# cap_mother_v1_0.net
KiCad netlist of a schematic drawn in EAGLE
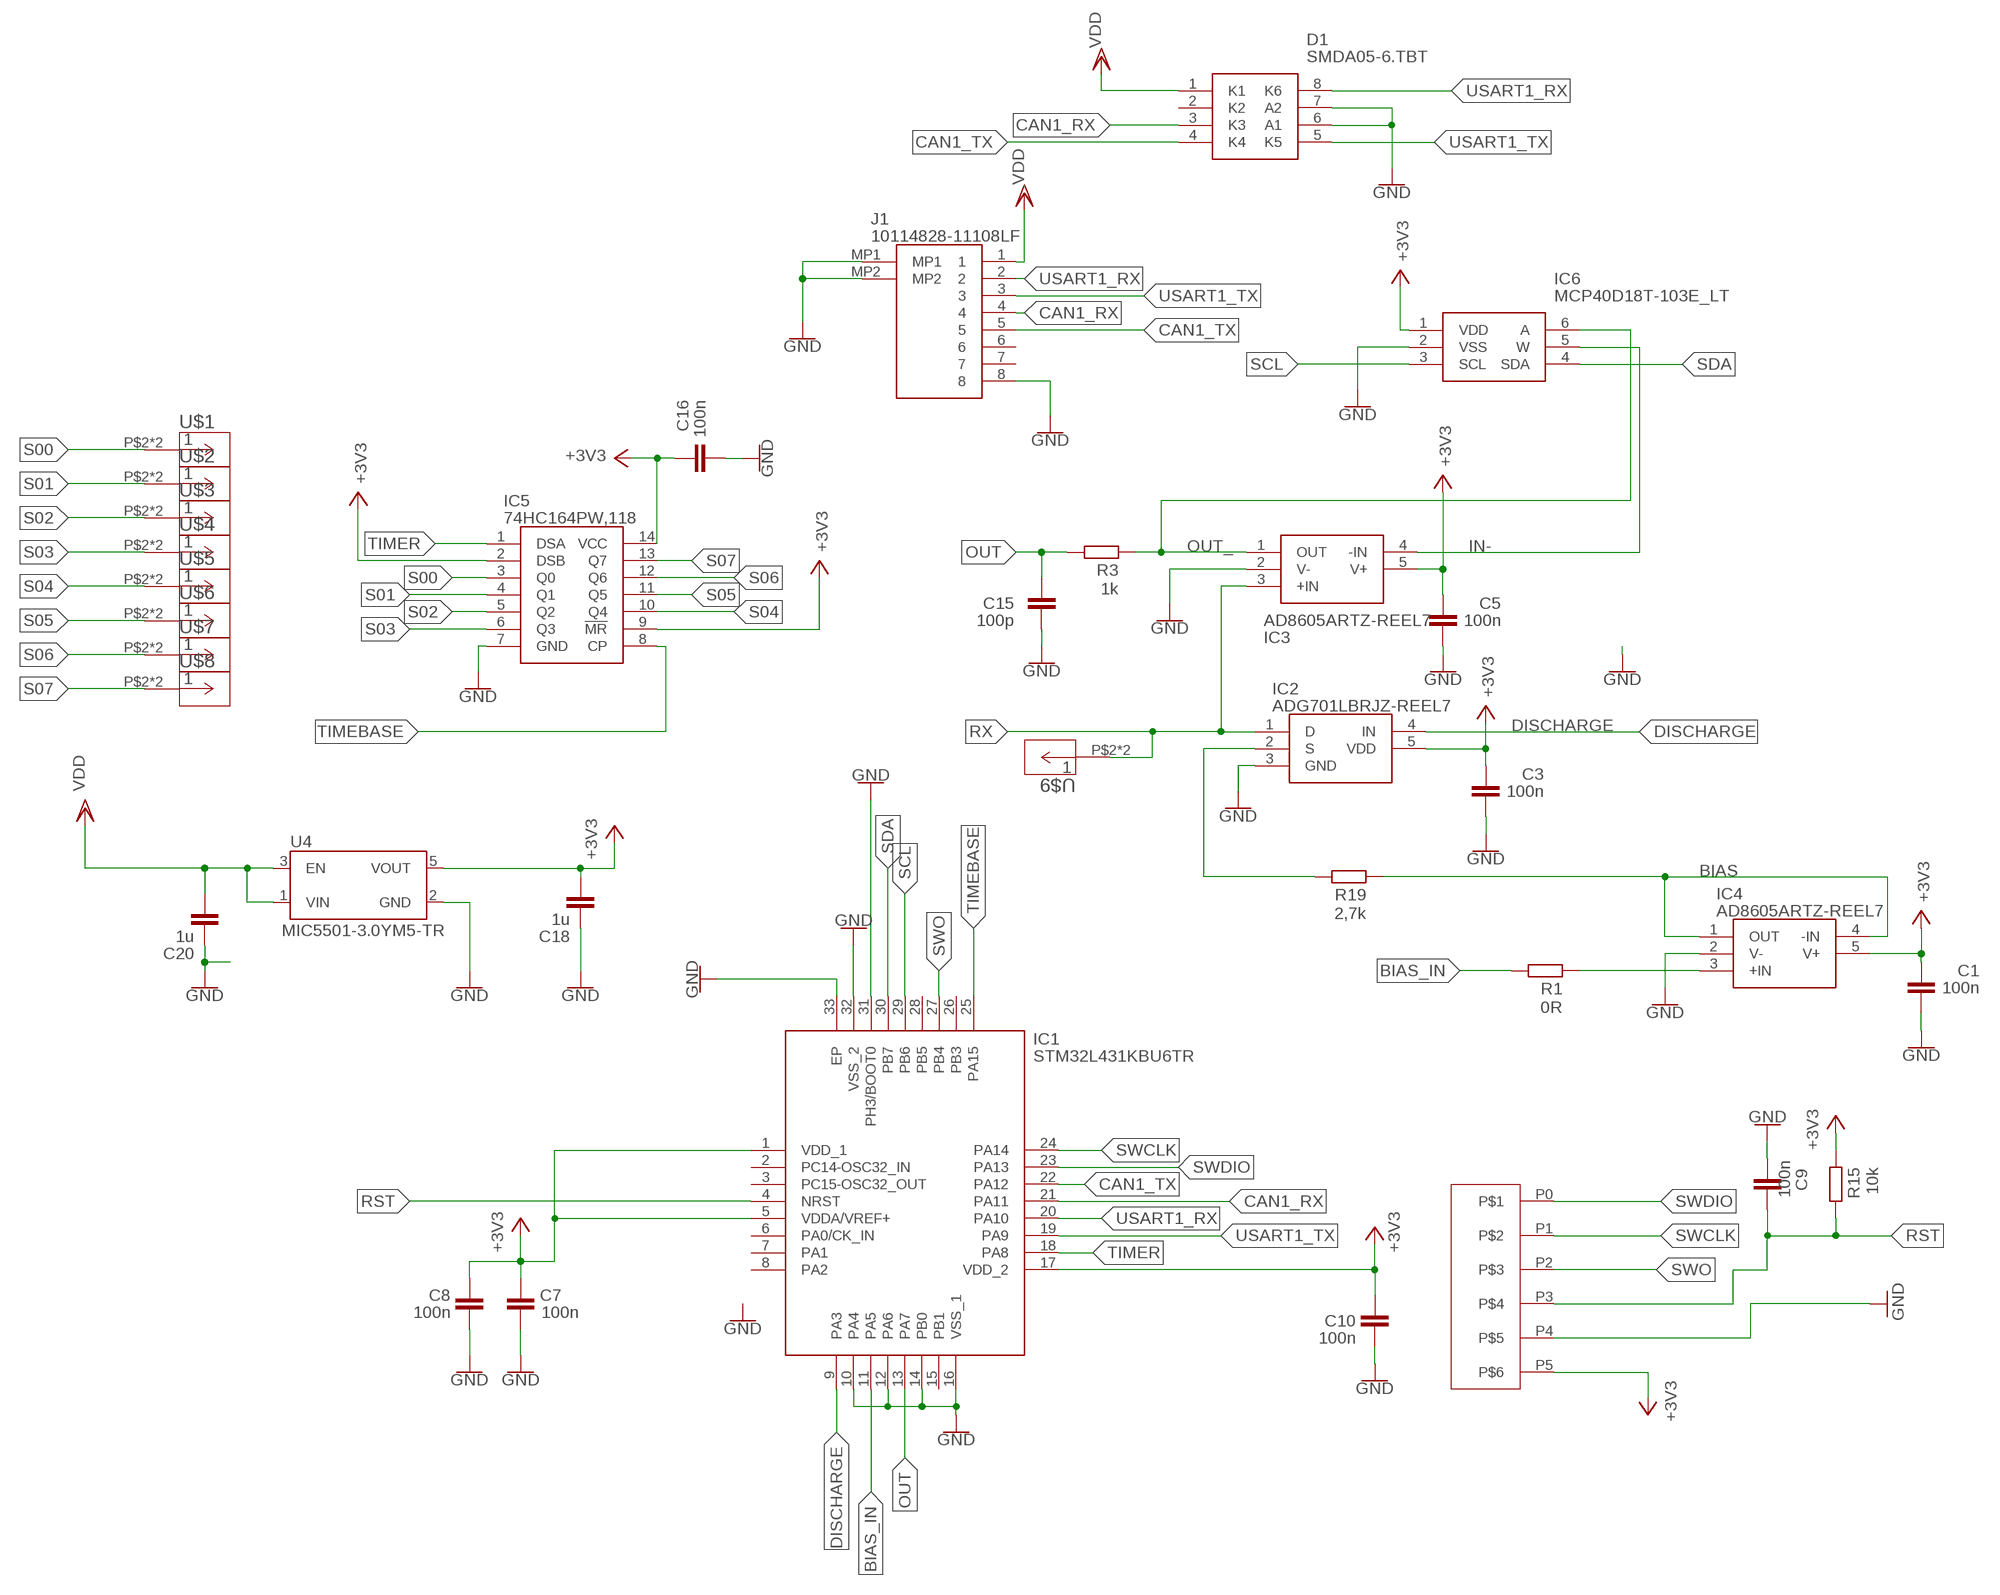
[diagram p0: schematic, sheet 1]

(export (version "E")
  (design (tool "Eeschema 10.0.6"))
  (components
    (comp (ref "C1")
      (value "100n")
      (footprint "eagle-import:C0603K")
      (libsource (lib "eagle-import") (part "rcl_334_C-EUC0603K"))
    )
    (comp (ref "C3")
      (value "100n")
      (footprint "eagle-import:C0603K")
      (libsource (lib "eagle-import") (part "rcl_334_C-EUC0603K"))
    )
    (comp (ref "C5")
      (value "100n")
      (footprint "eagle-import:C0603K")
      (libsource (lib "eagle-import") (part "rcl_334_C-EUC0603K"))
    )
    (comp (ref "C7")
      (value "100n")
      (footprint "eagle-import:C0603K")
      (libsource (lib "eagle-import") (part "rcl_334_C-EUC0603K"))
    )
    (comp (ref "C8")
      (value "100n")
      (footprint "eagle-import:C0603K")
      (libsource (lib "eagle-import") (part "rcl_334_C-EUC0603K"))
    )
    (comp (ref "C9")
      (value "100n")
      (footprint "eagle-import:C0603")
      (libsource (lib "eagle-import") (part "C-EUC0603"))
    )
    (comp (ref "C10")
      (value "100n")
      (footprint "eagle-import:C0603K")
      (libsource (lib "eagle-import") (part "rcl_334_C-EUC0603K"))
    )
    (comp (ref "C15")
      (value "100p")
      (footprint "eagle-import:C0603")
      (libsource (lib "eagle-import") (part "C-EUC0603"))
    )
    (comp (ref "C16")
      (value "100n")
      (footprint "eagle-import:C0603K")
      (libsource (lib "eagle-import") (part "rcl_334_C-EUC0603K"))
    )
    (comp (ref "C18")
      (value "1u")
      (footprint "eagle-import:C0603K")
      (libsource (lib "eagle-import") (part "rcl_334_C-EUC0603K"))
    )
    (comp (ref "C20")
      (value "1u")
      (footprint "eagle-import:C0603")
      (libsource (lib "eagle-import") (part "C-EUC0603"))
    )
    (comp (ref "D1")
      (value "SMDA05-6.TBT")
      (footprint "eagle-import:SOIC127P600X175-8N")
      (fields (field (name "MOUSER_PART_NUMBER") "947-SMDA05-6.TBT"))
      (libsource (lib "eagle-import") (part "SMDA05-6.TBT"))
    )
    (comp (ref "IC1")
      (value "STM32L431KBU6TR")
      (footprint "eagle-import:QFN50P500X500X60-33N")
      (fields (field (name "MOUSER_PART_NUMBER") "511-STM32L431KBU6TR"))
      (libsource (lib "eagle-import") (part "STM32L431KBU6TR"))
    )
    (comp (ref "IC2")
      (value "ADG701LBRJZ-REEL7")
      (footprint "eagle-import:SOT95P280X145-5N")
      (fields (field (name "MOUSER_PART_NUMBER") "584-ADG701LBRJZ-R7"))
      (libsource (lib "eagle-import") (part "ADG701LBRJZ-REEL7"))
    )
    (comp (ref "IC3")
      (value "AD8605ARTZ-REEL7")
      (footprint "eagle-import:SOT95P280X145-5N")
      (fields (field (name "MOUSER_PART_NUMBER") "584-AD8605ARTZ-R7"))
      (libsource (lib "eagle-import") (part "AD8605ARTZ-REEL7"))
    )
    (comp (ref "IC4")
      (value "AD8605ARTZ-REEL7")
      (footprint "eagle-import:SOT95P280X145-5N")
      (fields (field (name "MOUSER_PART_NUMBER") "584-AD8605ARTZ-R7"))
      (libsource (lib "eagle-import") (part "AD8605ARTZ-REEL7"))
    )
    (comp (ref "IC5")
      (value "74HC164PW,118")
      (footprint "eagle-import:SOP65P640X110-14N")
      (fields (field (name "MOUSER_PART_NUMBER") "771-74HC164PW-T"))
      (libsource (lib "eagle-import") (part "74HC164PW,118"))
    )
    (comp (ref "IC6")
      (value "MCP40D18T-103E_LT")
      (footprint "eagle-import:SOT65P210X110-6N")
      (fields
        (field (name "MANUFACTURER_PART_NUMBER") "MCP40D18T-103E/LT")
        (field (name "MOUSER_PART_NUMBER") "579-MCP40D18T103E/LT")
      )
      (libsource (lib "eagle-import") (part "MCP40D18T-103E_LT"))
    )
    (comp (ref "J1")
      (value "10114828-11108LF")
      (footprint "eagle-import:1011482811108LF")
      (fields (field (name "MOUSER_PART_NUMBER") "649-10114828-11108LF"))
      (libsource (lib "eagle-import") (part "10114828-11108LF"))
    )
    (comp (ref "R1")
      (value "0R")
      (footprint "eagle-import:R0603")
      (libsource (lib "eagle-import") (part "R-EU_R0603"))
    )
    (comp (ref "R3")
      (value "1k")
      (footprint "eagle-import:R0603")
      (libsource (lib "eagle-import") (part "R-EU_R0603"))
    )
    (comp (ref "R15")
      (value "10k")
      (footprint "eagle-import:R0603")
      (libsource (lib "eagle-import") (part "R-EU_R0603"))
    )
    (comp (ref "R19")
      (value "2,7k")
      (footprint "eagle-import:R0603")
      (libsource (lib "eagle-import") (part "R-EU_R0603"))
    )
    (comp (ref "U$1")
      (value "CAST_HOLE_1X1SHORT")
      (footprint "eagle-import:CASTELATED_HOLE_SHORT")
      (libsource (lib "eagle-import") (part "CAST_HOLE_1X1SHORT"))
    )
    (comp (ref "U$2")
      (value "CAST_HOLE_1X1SHORT")
      (footprint "eagle-import:CASTELATED_HOLE_SHORT")
      (libsource (lib "eagle-import") (part "CAST_HOLE_1X1SHORT"))
    )
    (comp (ref "U$3")
      (value "CAST_HOLE_1X1SHORT")
      (footprint "eagle-import:CASTELATED_HOLE_SHORT")
      (libsource (lib "eagle-import") (part "CAST_HOLE_1X1SHORT"))
    )
    (comp (ref "U$4")
      (value "CAST_HOLE_1X1SHORT")
      (footprint "eagle-import:CASTELATED_HOLE_SHORT")
      (libsource (lib "eagle-import") (part "CAST_HOLE_1X1SHORT"))
    )
    (comp (ref "U$5")
      (value "CAST_HOLE_1X1SHORT")
      (footprint "eagle-import:CASTELATED_HOLE_SHORT")
      (libsource (lib "eagle-import") (part "CAST_HOLE_1X1SHORT"))
    )
    (comp (ref "U$6")
      (value "CAST_HOLE_1X1SHORT")
      (footprint "eagle-import:CASTELATED_HOLE_SHORT")
      (libsource (lib "eagle-import") (part "CAST_HOLE_1X1SHORT"))
    )
    (comp (ref "U$7")
      (value "CAST_HOLE_1X1SHORT")
      (footprint "eagle-import:CASTELATED_HOLE_SHORT")
      (libsource (lib "eagle-import") (part "CAST_HOLE_1X1SHORT"))
    )
    (comp (ref "U$8")
      (value "CAST_HOLE_1X1SHORT")
      (footprint "eagle-import:CASTELATED_HOLE_SHORT")
      (libsource (lib "eagle-import") (part "CAST_HOLE_1X1SHORT"))
    )
    (comp (ref "U$9")
      (value "CAST_HOLE_1X1SHORT")
      (footprint "eagle-import:CASTELATED_HOLE_SHORT")
      (libsource (lib "eagle-import") (part "CAST_HOLE_1X1SHORT"))
    )
    (comp (ref "U$10")
      (value "SMD_SWO")
      (footprint "eagle-import:SWD_SMD")
      (libsource (lib "eagle-import") (part "SMD_SWO"))
    )
    (comp (ref "U4")
      (value "MIC5501-3.0YM5-TR")
      (footprint "eagle-import:SOT95P280X145-5N")
      (fields (field (name "MF") "Microchip"))
      (libsource (lib "eagle-import") (part "MIC5501-3.0YM5-TR"))
    )
  )
  (nets
    (net (code "1") (name "+3V3") (class "Default")
      (node (ref "C1") (pin "2") (pinfunction "2_2") (pintype "passive"))
      (node (ref "C10") (pin "2") (pinfunction "2_2") (pintype "passive"))
      (node (ref "C16") (pin "2") (pinfunction "2_2") (pintype "passive"))
      (node (ref "C18") (pin "2") (pinfunction "2_2") (pintype "passive"))
      (node (ref "C3") (pin "2") (pinfunction "2_2") (pintype "passive"))
      (node (ref "C5") (pin "2") (pinfunction "2_2") (pintype "passive"))
      (node (ref "C7") (pin "2") (pinfunction "2_2") (pintype "passive"))
      (node (ref "C8") (pin "2") (pinfunction "2_2") (pintype "passive"))
      (node (ref "IC1") (pin "1") (pinfunction "VDD_1_1") (pintype "bidirectional"))
      (node (ref "IC1") (pin "17") (pinfunction "VDD_2_17") (pintype "bidirectional"))
      (node (ref "IC1") (pin "5") (pinfunction "VDDA/VREF+_5") (pintype "bidirectional"))
      (node (ref "IC2") (pin "5") (pinfunction "VDD_5") (pintype "bidirectional"))
      (node (ref "IC3") (pin "5") (pinfunction "V+_5") (pintype "bidirectional"))
      (node (ref "IC4") (pin "5") (pinfunction "V+_5") (pintype "bidirectional"))
      (node (ref "IC5") (pin "14") (pinfunction "VCC_14") (pintype "bidirectional"))
      (node (ref "IC5") (pin "2") (pinfunction "DSB_2") (pintype "bidirectional"))
      (node (ref "IC5") (pin "9") (pinfunction "~{MR}_9") (pintype "bidirectional"))
      (node (ref "IC6") (pin "1") (pinfunction "VDD_1") (pintype "bidirectional"))
      (node (ref "R15") (pin "1") (pinfunction "1_1") (pintype "passive"))
      (node (ref "U$10") (pin "P5") (pinfunction "P$6_P5") (pintype "bidirectional"))
      (node (ref "U4") (pin "5") (pinfunction "VOUT_5") (pintype "output"))
    )
    (net (code "2") (name "/BIAS") (class "Default")
      (node (ref "IC4") (pin "1") (pinfunction "OUT_1") (pintype "bidirectional"))
      (node (ref "IC4") (pin "4") (pinfunction "-IN_4") (pintype "bidirectional"))
      (node (ref "R19") (pin "1") (pinfunction "1_1") (pintype "passive"))
    )
    (net (code "3") (name "/IN-") (class "Default")
      (node (ref "IC3") (pin "4") (pinfunction "-IN_4") (pintype "bidirectional"))
      (node (ref "IC6") (pin "5") (pinfunction "W_5") (pintype "bidirectional"))
    )
    (net (code "4") (name "/OUT_") (class "Default")
      (node (ref "IC3") (pin "1") (pinfunction "OUT_1") (pintype "bidirectional"))
      (node (ref "IC6") (pin "6") (pinfunction "A_6") (pintype "bidirectional"))
      (node (ref "R3") (pin "1") (pinfunction "1_1") (pintype "passive"))
    )
    (net (code "5") (name "BIAS_IN") (class "Default")
      (node (ref "IC1") (pin "11") (pinfunction "PA5_11") (pintype "bidirectional"))
      (node (ref "R1") (pin "2") (pinfunction "2_2") (pintype "passive"))
    )
    (net (code "6") (name "CAN1_RX") (class "Default")
      (node (ref "D1") (pin "3") (pinfunction "K3_3") (pintype "bidirectional"))
      (node (ref "IC1") (pin "21") (pinfunction "PA11_21") (pintype "bidirectional"))
      (node (ref "J1") (pin "4") (pinfunction "4_4") (pintype "bidirectional"))
    )
    (net (code "7") (name "CAN1_TX") (class "Default")
      (node (ref "D1") (pin "4") (pinfunction "K4_4") (pintype "bidirectional"))
      (node (ref "IC1") (pin "22") (pinfunction "PA12_22") (pintype "bidirectional"))
      (node (ref "J1") (pin "5") (pinfunction "5_5") (pintype "bidirectional"))
    )
    (net (code "8") (name "DISCHARGE") (class "Default")
      (node (ref "IC1") (pin "9") (pinfunction "PA3_9") (pintype "bidirectional"))
      (node (ref "IC2") (pin "4") (pinfunction "IN_4") (pintype "bidirectional"))
    )
    (net (code "9") (name "GND") (class "Default")
      (node (ref "C1") (pin "1") (pinfunction "1_1") (pintype "passive"))
      (node (ref "C10") (pin "1") (pinfunction "1_1") (pintype "passive"))
      (node (ref "C15") (pin "1") (pinfunction "1_1") (pintype "passive"))
      (node (ref "C16") (pin "1") (pinfunction "1_1") (pintype "passive"))
      (node (ref "C18") (pin "1") (pinfunction "1_1") (pintype "passive"))
      (node (ref "C20") (pin "1") (pinfunction "1_1") (pintype "passive"))
      (node (ref "C3") (pin "1") (pinfunction "1_1") (pintype "passive"))
      (node (ref "C5") (pin "1") (pinfunction "1_1") (pintype "passive"))
      (node (ref "C7") (pin "1") (pinfunction "1_1") (pintype "passive"))
      (node (ref "C8") (pin "1") (pinfunction "1_1") (pintype "passive"))
      (node (ref "C9") (pin "1") (pinfunction "1_1") (pintype "passive"))
      (node (ref "D1") (pin "6") (pinfunction "A1_6") (pintype "bidirectional"))
      (node (ref "D1") (pin "7") (pinfunction "A2_7") (pintype "bidirectional"))
      (node (ref "IC1") (pin "10") (pinfunction "PA4_10") (pintype "bidirectional"))
      (node (ref "IC1") (pin "12") (pinfunction "PA6_12") (pintype "bidirectional"))
      (node (ref "IC1") (pin "14") (pinfunction "PB0_14") (pintype "bidirectional"))
      (node (ref "IC1") (pin "16") (pinfunction "VSS_1_16") (pintype "bidirectional"))
      (node (ref "IC1") (pin "31") (pinfunction "PH3/BOOT0_31") (pintype "bidirectional"))
      (node (ref "IC1") (pin "32") (pinfunction "VSS_2_32") (pintype "bidirectional"))
      (node (ref "IC1") (pin "33") (pinfunction "EP_33") (pintype "bidirectional"))
      (node (ref "IC2") (pin "3") (pinfunction "GND_3") (pintype "bidirectional"))
      (node (ref "IC3") (pin "2") (pinfunction "V-_2") (pintype "bidirectional"))
      (node (ref "IC4") (pin "2") (pinfunction "V-_2") (pintype "bidirectional"))
      (node (ref "IC5") (pin "7") (pinfunction "GND_7") (pintype "bidirectional"))
      (node (ref "IC6") (pin "2") (pinfunction "VSS_2") (pintype "bidirectional"))
      (node (ref "J1") (pin "8") (pinfunction "8_8") (pintype "bidirectional"))
      (node (ref "J1") (pin "MP1") (pinfunction "MP1_MP1") (pintype "bidirectional"))
      (node (ref "J1") (pin "MP2") (pinfunction "MP2_MP2") (pintype "bidirectional"))
      (node (ref "U$10") (pin "P4") (pinfunction "P$5_P4") (pintype "bidirectional"))
      (node (ref "U4") (pin "2") (pinfunction "GND_2") (pintype "power_in"))
    )
    (net (code "10") (name "Net-(IC2-S)") (class "Default")
      (node (ref "IC2") (pin "2") (pinfunction "S_2") (pintype "bidirectional"))
      (node (ref "R19") (pin "2") (pinfunction "2_2") (pintype "passive"))
    )
    (net (code "11") (name "Net-(IC4-+IN)") (class "Default")
      (node (ref "IC4") (pin "3") (pinfunction "+IN_3") (pintype "bidirectional"))
      (node (ref "R1") (pin "1") (pinfunction "1_1") (pintype "passive"))
    )
    (net (code "12") (name "OUT") (class "Default")
      (node (ref "C15") (pin "2") (pinfunction "2_2") (pintype "passive"))
      (node (ref "IC1") (pin "13") (pinfunction "PA7_13") (pintype "bidirectional"))
      (node (ref "R3") (pin "2") (pinfunction "2_2") (pintype "passive"))
    )
    (net (code "13") (name "RST") (class "Default")
      (node (ref "C9") (pin "2") (pinfunction "2_2") (pintype "passive"))
      (node (ref "IC1") (pin "4") (pinfunction "NRST_4") (pintype "bidirectional"))
      (node (ref "R15") (pin "2") (pinfunction "2_2") (pintype "passive"))
      (node (ref "U$10") (pin "P3") (pinfunction "P$4_P3") (pintype "bidirectional"))
    )
    (net (code "14") (name "RX") (class "Default")
      (node (ref "IC2") (pin "1") (pinfunction "D_1") (pintype "bidirectional"))
      (node (ref "IC3") (pin "3") (pinfunction "+IN_3") (pintype "bidirectional"))
      (node (ref "U$9") (pin "P$2") (pinfunction "1_P$2") (pintype "passive"))
      (node (ref "U$9") (pin "P$3") (pinfunction "1_P$3") (pintype "passive"))
    )
    (net (code "15") (name "S00") (class "Default")
      (node (ref "IC5") (pin "3") (pinfunction "Q0_3") (pintype "bidirectional"))
      (node (ref "U$1") (pin "P$2") (pinfunction "1_P$2") (pintype "passive"))
      (node (ref "U$1") (pin "P$3") (pinfunction "1_P$3") (pintype "passive"))
    )
    (net (code "16") (name "S01") (class "Default")
      (node (ref "IC5") (pin "4") (pinfunction "Q1_4") (pintype "bidirectional"))
      (node (ref "U$2") (pin "P$2") (pinfunction "1_P$2") (pintype "passive"))
      (node (ref "U$2") (pin "P$3") (pinfunction "1_P$3") (pintype "passive"))
    )
    (net (code "17") (name "S02") (class "Default")
      (node (ref "IC5") (pin "5") (pinfunction "Q2_5") (pintype "bidirectional"))
      (node (ref "U$3") (pin "P$2") (pinfunction "1_P$2") (pintype "passive"))
      (node (ref "U$3") (pin "P$3") (pinfunction "1_P$3") (pintype "passive"))
    )
    (net (code "18") (name "S03") (class "Default")
      (node (ref "IC5") (pin "6") (pinfunction "Q3_6") (pintype "bidirectional"))
      (node (ref "U$4") (pin "P$2") (pinfunction "1_P$2") (pintype "passive"))
      (node (ref "U$4") (pin "P$3") (pinfunction "1_P$3") (pintype "passive"))
    )
    (net (code "19") (name "S04") (class "Default")
      (node (ref "IC5") (pin "10") (pinfunction "Q4_10") (pintype "bidirectional"))
      (node (ref "U$5") (pin "P$2") (pinfunction "1_P$2") (pintype "passive"))
      (node (ref "U$5") (pin "P$3") (pinfunction "1_P$3") (pintype "passive"))
    )
    (net (code "20") (name "S05") (class "Default")
      (node (ref "IC5") (pin "11") (pinfunction "Q5_11") (pintype "bidirectional"))
      (node (ref "U$6") (pin "P$2") (pinfunction "1_P$2") (pintype "passive"))
      (node (ref "U$6") (pin "P$3") (pinfunction "1_P$3") (pintype "passive"))
    )
    (net (code "21") (name "S06") (class "Default")
      (node (ref "IC5") (pin "12") (pinfunction "Q6_12") (pintype "bidirectional"))
      (node (ref "U$7") (pin "P$2") (pinfunction "1_P$2") (pintype "passive"))
      (node (ref "U$7") (pin "P$3") (pinfunction "1_P$3") (pintype "passive"))
    )
    (net (code "22") (name "S07") (class "Default")
      (node (ref "IC5") (pin "13") (pinfunction "Q7_13") (pintype "bidirectional"))
      (node (ref "U$8") (pin "P$2") (pinfunction "1_P$2") (pintype "passive"))
      (node (ref "U$8") (pin "P$3") (pinfunction "1_P$3") (pintype "passive"))
    )
    (net (code "23") (name "SCL") (class "Default")
      (node (ref "IC1") (pin "29") (pinfunction "PB6_29") (pintype "bidirectional"))
      (node (ref "IC6") (pin "3") (pinfunction "SCL_3") (pintype "bidirectional"))
    )
    (net (code "24") (name "SDA") (class "Default")
      (node (ref "IC1") (pin "30") (pinfunction "PB7_30") (pintype "bidirectional"))
      (node (ref "IC6") (pin "4") (pinfunction "SDA_4") (pintype "bidirectional"))
    )
    (net (code "25") (name "SWCLK") (class "Default")
      (node (ref "IC1") (pin "24") (pinfunction "PA14_24") (pintype "bidirectional"))
      (node (ref "U$10") (pin "P1") (pinfunction "P$2_P1") (pintype "bidirectional"))
    )
    (net (code "26") (name "SWDIO") (class "Default")
      (node (ref "IC1") (pin "23") (pinfunction "PA13_23") (pintype "bidirectional"))
      (node (ref "U$10") (pin "P0") (pinfunction "P$1_P0") (pintype "bidirectional"))
    )
    (net (code "27") (name "SWO") (class "Default")
      (node (ref "IC1") (pin "27") (pinfunction "PB4_27") (pintype "bidirectional"))
      (node (ref "U$10") (pin "P2") (pinfunction "P$3_P2") (pintype "bidirectional"))
    )
    (net (code "28") (name "TIMEBASE") (class "Default")
      (node (ref "IC1") (pin "25") (pinfunction "PA15_25") (pintype "bidirectional"))
      (node (ref "IC5") (pin "8") (pinfunction "CP_8") (pintype "bidirectional"))
    )
    (net (code "29") (name "TIMER") (class "Default")
      (node (ref "IC1") (pin "18") (pinfunction "PA8_18") (pintype "bidirectional"))
      (node (ref "IC5") (pin "1") (pinfunction "DSA_1") (pintype "bidirectional"))
    )
    (net (code "30") (name "USART1_RX") (class "Default")
      (node (ref "D1") (pin "8") (pinfunction "K6_8") (pintype "bidirectional"))
      (node (ref "IC1") (pin "20") (pinfunction "PA10_20") (pintype "bidirectional"))
      (node (ref "J1") (pin "2") (pinfunction "2_2") (pintype "bidirectional"))
    )
    (net (code "31") (name "USART1_TX") (class "Default")
      (node (ref "D1") (pin "5") (pinfunction "K5_5") (pintype "bidirectional"))
      (node (ref "IC1") (pin "19") (pinfunction "PA9_19") (pintype "bidirectional"))
      (node (ref "J1") (pin "3") (pinfunction "3_3") (pintype "bidirectional"))
    )
    (net (code "32") (name "VDD") (class "Default")
      (node (ref "C20") (pin "2") (pinfunction "2_2") (pintype "passive"))
      (node (ref "D1") (pin "1") (pinfunction "K1_1") (pintype "bidirectional"))
      (node (ref "J1") (pin "1") (pinfunction "1_1") (pintype "bidirectional"))
      (node (ref "U4") (pin "1") (pinfunction "VIN_1") (pintype "input"))
      (node (ref "U4") (pin "3") (pinfunction "EN_3") (pintype "input"))
    )
    (net (code "33") (name "unconnected-(D1-K2-Pad2)") (class "Default")
      (node (ref "D1") (pin "2") (pinfunction "K2_2") (pintype "bidirectional"))
    )
    (net (code "34") (name "unconnected-(IC1-PA0{slash}CK_IN-Pad6)") (class "Default")
      (node (ref "IC1") (pin "6") (pinfunction "PA0/CK_IN_6") (pintype "bidirectional"))
    )
    (net (code "35") (name "unconnected-(IC1-PA1-Pad7)") (class "Default")
      (node (ref "IC1") (pin "7") (pinfunction "PA1_7") (pintype "bidirectional"))
    )
    (net (code "36") (name "unconnected-(IC1-PA2-Pad8)") (class "Default")
      (node (ref "IC1") (pin "8") (pinfunction "PA2_8") (pintype "bidirectional"))
    )
    (net (code "37") (name "unconnected-(IC1-PB1-Pad15)") (class "Default")
      (node (ref "IC1") (pin "15") (pinfunction "PB1_15") (pintype "bidirectional"))
    )
    (net (code "38") (name "unconnected-(IC1-PB3-Pad26)") (class "Default")
      (node (ref "IC1") (pin "26") (pinfunction "PB3_26") (pintype "bidirectional"))
    )
    (net (code "39") (name "unconnected-(IC1-PB5-Pad28)") (class "Default")
      (node (ref "IC1") (pin "28") (pinfunction "PB5_28") (pintype "bidirectional"))
    )
    (net (code "40") (name "unconnected-(IC1-PC14-OSC32_IN-Pad2)") (class "Default")
      (node (ref "IC1") (pin "2") (pinfunction "PC14-OSC32_IN_2") (pintype "bidirectional"))
    )
    (net (code "41") (name "unconnected-(IC1-PC15-OSC32_OUT-Pad3)") (class "Default")
      (node (ref "IC1") (pin "3") (pinfunction "PC15-OSC32_OUT_3") (pintype "bidirectional"))
    )
    (net (code "42") (name "unconnected-(J1-Pad6)") (class "Default")
      (node (ref "J1") (pin "6") (pinfunction "6_6") (pintype "bidirectional"))
    )
    (net (code "43") (name "unconnected-(J1-Pad7)") (class "Default")
      (node (ref "J1") (pin "7") (pinfunction "7_7") (pintype "bidirectional"))
    )
  )
)
